# 5vInlinePSU.net
KiCad netlist of a schematic drawn in EAGLE
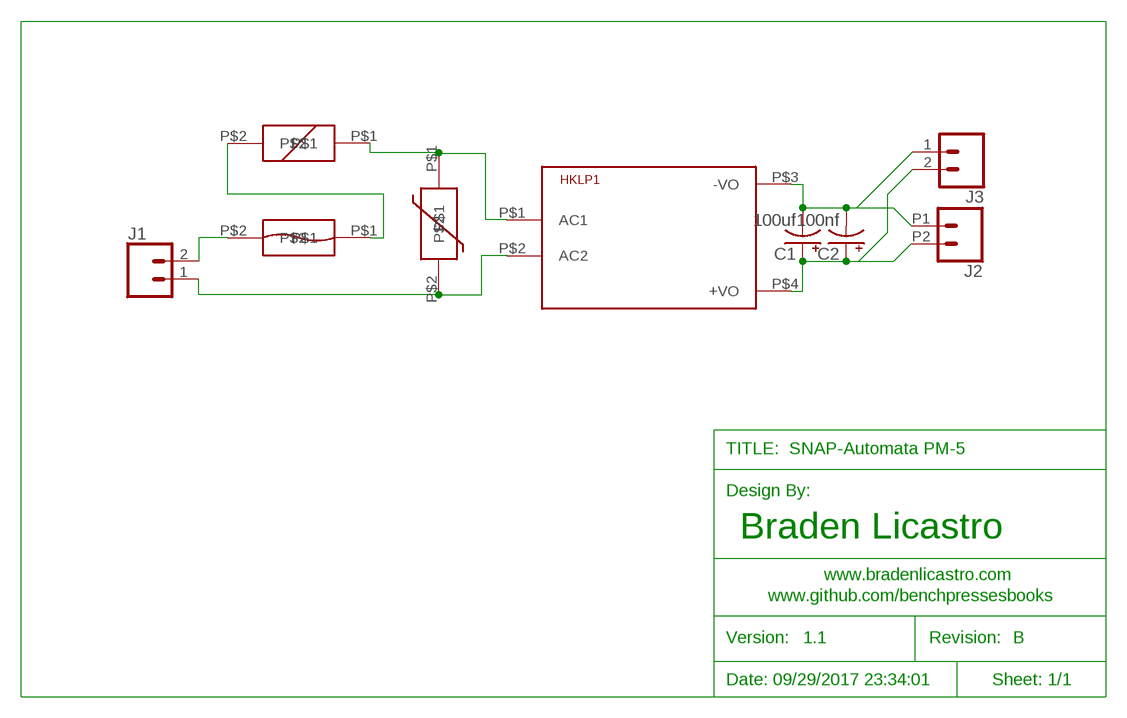
[diagram p0: schematic, sheet 1]

(export (version "E")
  (design (tool "Eeschema 10.0.6"))
  (components
    (comp (ref "C1")
      (value "100uf")
      (footprint "eagle-import:E5-8,5")
      (libsource (lib "eagle-import") (part "CPOL-USE5-8.5"))
    )
    (comp (ref "C2")
      (value "100nf")
      (footprint "eagle-import:E2,5-6")
      (libsource (lib "eagle-import") (part "CPOL-USE2.5-6"))
    )
    (comp (ref "HKLP1")
      (value "HKLPM01")
      (footprint "eagle-import:HKLPM01")
      (libsource (lib "eagle-import") (part "HKLPM01"))
    )
    (comp (ref "J1")
      (value "CONN_025MM")
      (footprint "eagle-import:SCREWTERMINAL-5MM-2")
      (libsource (lib "eagle-import") (part "CONN_025MM"))
    )
    (comp (ref "J2")
      (value "CONN_022.54MM_SCREWTERM")
      (footprint "eagle-import:1X02_2.54_SCREWTERM")
      (libsource (lib "eagle-import") (part "CONN_022.54MM_SCREWTERM"))
    )
    (comp (ref "J3")
      (value "CONN_02")
      (footprint "eagle-import:1X02")
      (libsource (lib "eagle-import") (part "CONN_02"))
    )
    (comp (ref "SDF")
      (value "GENERIC_FUSE_3.6X10MMTHROUGH-HOLE")
      (footprint "eagle-import:GENERIC_FUSE_3.6X10MM")
      (libsource (lib "eagle-import") (part "GENERIC_FUSE_3.6X10MMTHROUGH-HOLE"))
    )
    (comp (ref "U$2")
      (value "THERMAL_FUSE_SF70ETHROUGH-HOLE")
      (footprint "eagle-import:THERMAL_FUSE_SF70E")
      (libsource (lib "eagle-import") (part "THERMAL_FUSE_SF70ETHROUGH-HOLE"))
    )
    (comp (ref "U$3")
      (value "VARISTOR_TVR-07241THROUGH-HOLE")
      (footprint "eagle-import:VARISTOR_TVR-07241")
      (libsource (lib "eagle-import") (part "VARISTOR_TVR-07241THROUGH-HOLE"))
    )
  )
  (nets
    (net (code "1") (name "Net-(HKLP1-+VO)") (class "Default")
      (node (ref "C1") (pin "+") (pinfunction "+_+") (pintype "passive"))
      (node (ref "C2") (pin "+") (pinfunction "+_+") (pintype "passive"))
      (node (ref "HKLP1") (pin "P$4") (pinfunction "+VO_P$4") (pintype "output"))
      (node (ref "J2") (pin "P2") (pinfunction "2_P2") (pintype "passive"))
      (node (ref "J3") (pin "2") (pinfunction "2_2") (pintype "passive"))
    )
    (net (code "2") (name "Net-(HKLP1--VO)") (class "Default")
      (node (ref "C1") (pin "-") (pinfunction "-_-") (pintype "passive"))
      (node (ref "C2") (pin "-") (pinfunction "-_-") (pintype "passive"))
      (node (ref "HKLP1") (pin "P$3") (pinfunction "-VO_P$3") (pintype "output"))
      (node (ref "J2") (pin "P1") (pinfunction "1_P1") (pintype "passive"))
      (node (ref "J3") (pin "1") (pinfunction "1_1") (pintype "passive"))
    )
    (net (code "3") (name "Net-(HKLP1-AC1)") (class "Default")
      (node (ref "HKLP1") (pin "P$1") (pinfunction "AC1_P$1") (pintype "input"))
      (node (ref "U$2") (pin "P$1") (pinfunction "P$1_P$1") (pintype "bidirectional"))
      (node (ref "U$3") (pin "P$1") (pinfunction "P$1_P$1") (pintype "bidirectional"))
    )
    (net (code "4") (name "Net-(HKLP1-AC2)") (class "Default")
      (node (ref "HKLP1") (pin "P$2") (pinfunction "AC2_P$2") (pintype "input"))
      (node (ref "J1") (pin "1") (pinfunction "1_1") (pintype "passive"))
      (node (ref "U$3") (pin "P$2") (pinfunction "P$2_P$2") (pintype "bidirectional"))
    )
    (net (code "5") (name "Net-(J1-Pad2)") (class "Default")
      (node (ref "J1") (pin "2") (pinfunction "2_2") (pintype "passive"))
      (node (ref "SDF") (pin "P$2") (pinfunction "P$2_P$2") (pintype "bidirectional"))
    )
    (net (code "6") (name "Net-(SDF-PadP$1)") (class "Default")
      (node (ref "SDF") (pin "P$1") (pinfunction "P$1_P$1") (pintype "bidirectional"))
      (node (ref "U$2") (pin "P$2") (pinfunction "P$2_P$2") (pintype "bidirectional"))
    )
  )
)
